# RB_Audio.net
KiCad netlist of a schematic drawn in Altium Designer
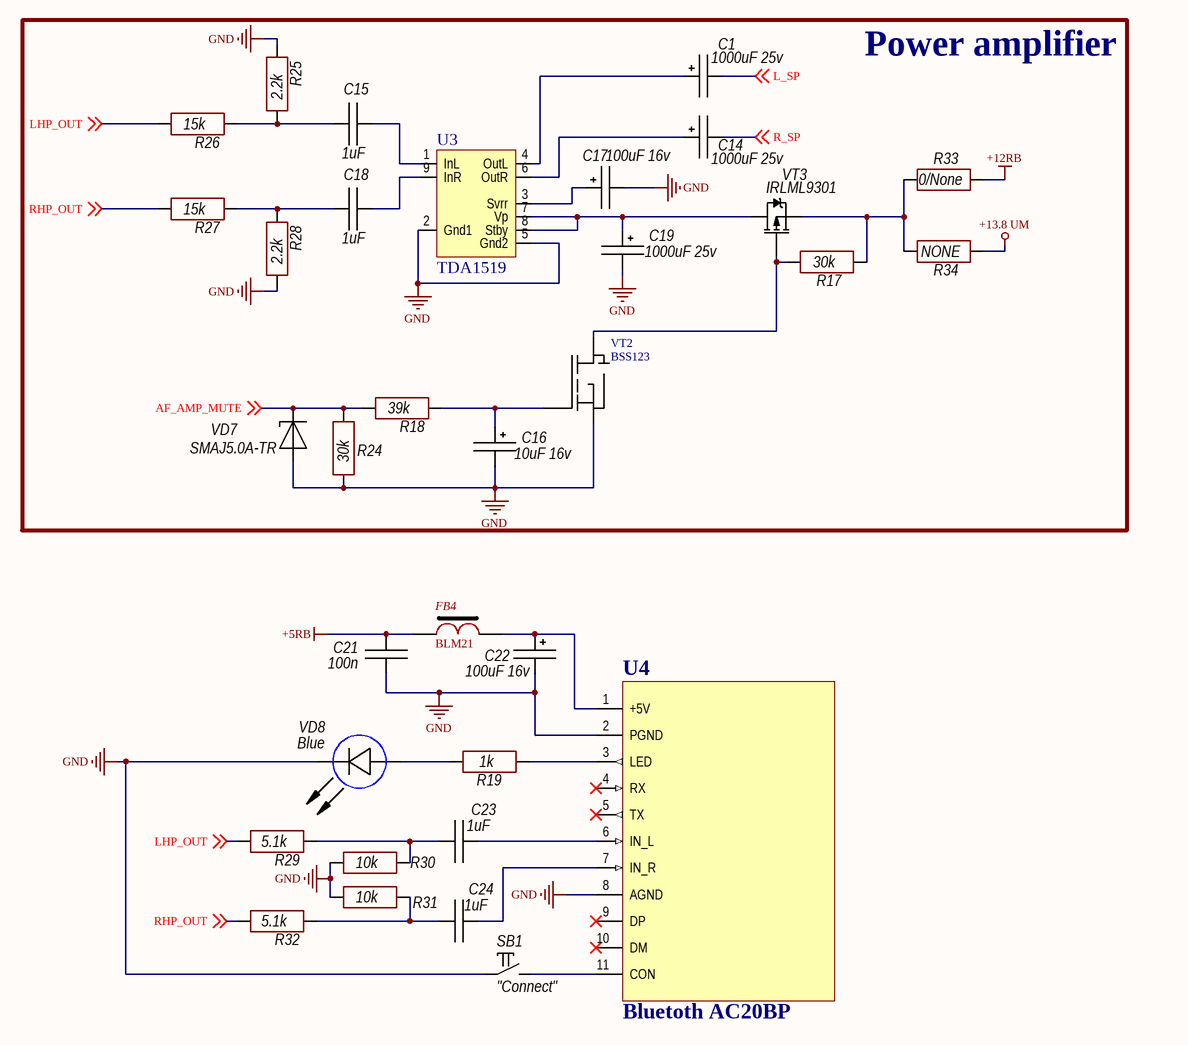
[diagram p0: RB_Audio.SchDoc]

(export (version "E")
  (design (tool "Eeschema 10.0.6"))
  (components
    (comp (ref "C1")
      (value "1000uF 25v")
      (footprint "standard:D10C5H12.5")
      (libsource (lib "Discrete") (part "AlumCap"))
    )
    (comp (ref "C14")
      (value "1000uF 25v")
      (footprint "standard:D10C5H12.5")
      (libsource (lib "") (part "AlumCap_1"))
    )
    (comp (ref "C15")
      (value "1uF")
      (footprint "standard:CH0805C")
      (libsource (lib "Discrete") (part "Capacitor"))
    )
    (comp (ref "C16")
      (value "10uF 16v")
      (footprint "standard:TANTAL_B")
      (libsource (lib "Discrete") (part "TantalCap"))
    )
    (comp (ref "C17")
      (value "100uF 16v")
      (footprint "standard:TANTAL_D")
      (libsource (lib "Discrete") (part "TantalCap"))
    )
    (comp (ref "C18")
      (value "1uF")
      (footprint "standard:CH0805C")
      (libsource (lib "Discrete") (part "Capacitor"))
    )
    (comp (ref "C19")
      (value "1000uF 25v")
      (footprint "standard:D10C5H12.5")
      (libsource (lib "Discrete") (part "AlumCap"))
    )
    (comp (ref "C21")
      (value "100n")
      (footprint "standard:CH0805C")
      (libsource (lib "Discrete") (part "Capacitor"))
    )
    (comp (ref "C22")
      (value "100uF 16v")
      (footprint "standard:D6.3C2.5H11")
      (libsource (lib "Discrete") (part "AlumCap"))
    )
    (comp (ref "C23")
      (value "1uF")
      (footprint "standard:CH0805C")
      (libsource (lib "Discrete") (part "Capacitor"))
    )
    (comp (ref "C24")
      (value "1uF")
      (footprint "standard:CH0805C")
      (libsource (lib "Discrete") (part "Capacitor"))
    )
    (comp (ref "FB4") (value "BLM21") (footprint "CH0805L") (libsource (lib "Discrete") (part "FB-1")))
    (comp (ref "R17") (value "30k") (footprint "standard:CH0805R") (libsource (lib "") (part "Resistor_1")))
    (comp (ref "R18") (value "39k") (footprint "standard:CH0805R") (libsource (lib "") (part "Resistor_1")))
    (comp (ref "R19") (value "1k") (footprint "standard:CH0805R") (libsource (lib "") (part "Resistor_1")))
    (comp (ref "R24")
      (value "30k")
      (footprint "standard:CH0805R")
      (libsource (lib "Discrete") (part "Resistor"))
    )
    (comp (ref "R25")
      (value "2.2k")
      (footprint "standard:CH0805R")
      (libsource (lib "Discrete") (part "Resistor"))
    )
    (comp (ref "R26") (value "15k") (footprint "standard:CH0805R") (libsource (lib "") (part "Resistor_1")))
    (comp (ref "R27") (value "15k") (footprint "standard:CH0805R") (libsource (lib "") (part "Resistor_1")))
    (comp (ref "R28") (value "2.2k") (footprint "standard:CH0805R") (libsource (lib "") (part "Resistor_2")))
    (comp (ref "R29") (value "5.1k") (footprint "standard:CH0805R") (libsource (lib "") (part "Resistor_1")))
    (comp (ref "R30") (value "10k") (footprint "standard:CH0805R") (libsource (lib "") (part "Resistor_1")))
    (comp (ref "R31") (value "10k") (footprint "standard:CH0805R") (libsource (lib "") (part "Resistor_1")))
    (comp (ref "R32") (value "5.1k") (footprint "standard:CH0805R") (libsource (lib "") (part "Resistor_1")))
    (comp (ref "R33")
      (value "0/None")
      (footprint "standard:CH1206R")
      (libsource (lib "") (part "Resistor_1"))
    )
    (comp (ref "R34") (value "NONE") (footprint "standard:CH1206R") (libsource (lib "") (part "Resistor_1")))
    (comp (ref "SB1")
      (value "\"Connect\"")
      (footprint "custom:BUT: 6x6 mm (R)")
      (description "6x6 mm")
      (libsource (lib "Connectors") (part "Tactile switches"))
    )
    (comp (ref "U3") (value "TDA1519") (footprint "SOT110B") (libsource (lib "Discrete") (part "TDA1519")))
    (comp (ref "U4")
      (value "Bluetoth AC20BP")
      (footprint "Bluetooth 11PIN")
      (libsource (lib "Module") (part "Bluetoth AC20BP Module"))
    )
    (comp (ref "VD7")
      (value "SMAJ5.0A-TR")
      (footprint "standard:SMA")
      (libsource (lib "Diods") (part "Diod Zener"))
    )
    (comp (ref "VD8")
      (value "Blue")
      (footprint "standard:CH0805LB")
      (libsource (lib "Discrete") (part "LED"))
    )
    (comp (ref "VT2") (value "BSS123") (footprint "SOT23_132") (libsource (lib "Transistor") (part "BSS123")))
    (comp (ref "VT3")
      (value "IRLML9301")
      (footprint "standard:SOT23_132")
      (description "Mosfet")
      (libsource (lib "Transistor") (part "IRLML9301"))
    )
  )
  (nets
    (net (code "1") (name "+5RB") (class "Default")
      (node (ref "C21") (pin "2") (pinfunction "2_2") (pintype "power_in"))
      (node (ref "FB4") (pin "2") (pinfunction "2_2") (pintype "passive"))
    )
    (net (code "2") (name "+12RB") (class "Default")
      (node (ref "R33") (pin "2") (pinfunction "2_2") (pintype "passive"))
    )
    (net (code "3") (name "+13.8 UM") (class "Default")
      (node (ref "R34") (pin "2") (pinfunction "2_2") (pintype "passive"))
    )
    (net (code "4") (name "AF_AMP_MUTE") (class "Default")
      (node (ref "R18") (pin "1") (pinfunction "1_1") (pintype "passive"))
      (node (ref "R24") (pin "2") (pinfunction "2_2") (pintype "passive"))
      (node (ref "VD7") (pin "2") (pinfunction "C_2") (pintype "passive"))
    )
    (net (code "5") (name "GND") (class "Default")
      (node (ref "C16") (pin "2") (pinfunction "2_2") (pintype "power_in"))
      (node (ref "C17") (pin "2") (pinfunction "2_2") (pintype "power_in"))
      (node (ref "C19") (pin "2") (pinfunction "2_2") (pintype "power_in"))
      (node (ref "C21") (pin "1") (pinfunction "1_1") (pintype "power_in"))
      (node (ref "C22") (pin "2") (pinfunction "2_2") (pintype "power_in"))
      (node (ref "R24") (pin "1") (pinfunction "1_1") (pintype "passive"))
      (node (ref "R25") (pin "2") (pinfunction "2_2") (pintype "passive"))
      (node (ref "R28") (pin "1") (pinfunction "1_1") (pintype "passive"))
      (node (ref "R30") (pin "1") (pinfunction "1_1") (pintype "passive"))
      (node (ref "R31") (pin "1") (pinfunction "1_1") (pintype "passive"))
      (node (ref "SB1") (pin "1") (pinfunction "1_1") (pintype "passive"))
      (node (ref "U3") (pin "2") (pinfunction "Gnd1_2") (pintype "passive"))
      (node (ref "U3") (pin "5") (pinfunction "Gnd2_5") (pintype "passive"))
      (node (ref "U4") (pin "2") (pinfunction "PGND_2") (pintype "passive"))
      (node (ref "U4") (pin "8") (pinfunction "AGND_8") (pintype "passive"))
      (node (ref "VD7") (pin "1") (pinfunction "A_1") (pintype "passive"))
      (node (ref "VD8") (pin "2") (pinfunction "C_2") (pintype "passive"))
      (node (ref "VT2") (pin "2") (pinfunction "S_2") (pintype "passive"))
    )
    (net (code "6") (name "LHP_OUT") (class "Default")
      (node (ref "R26") (pin "1") (pinfunction "1_1") (pintype "passive"))
      (node (ref "R29") (pin "1") (pinfunction "1_1") (pintype "passive"))
    )
    (net (code "7") (name "L_SP") (class "Default")
      (node (ref "C1") (pin "2") (pinfunction "2_2") (pintype "power_in"))
    )
    (net (code "8") (name "Net-(C15-Pad1)") (class "Default")
      (node (ref "C15") (pin "1") (pinfunction "1_1") (pintype "power_in"))
      (node (ref "R25") (pin "1") (pinfunction "1_1") (pintype "passive"))
      (node (ref "R26") (pin "2") (pinfunction "2_2") (pintype "passive"))
    )
    (net (code "9") (name "Net-(C18-Pad1)") (class "Default")
      (node (ref "C18") (pin "1") (pinfunction "1_1") (pintype "power_in"))
      (node (ref "R27") (pin "2") (pinfunction "2_2") (pintype "passive"))
      (node (ref "R28") (pin "2") (pinfunction "2_2") (pintype "passive"))
    )
    (net (code "10") (name "Net-(C23-Pad1)") (class "Default")
      (node (ref "C23") (pin "1") (pinfunction "1_1") (pintype "power_in"))
      (node (ref "R29") (pin "2") (pinfunction "2_2") (pintype "passive"))
      (node (ref "R30") (pin "2") (pinfunction "2_2") (pintype "passive"))
    )
    (net (code "11") (name "Net-(C24-Pad1)") (class "Default")
      (node (ref "C24") (pin "1") (pinfunction "1_1") (pintype "power_in"))
      (node (ref "R31") (pin "2") (pinfunction "2_2") (pintype "passive"))
      (node (ref "R32") (pin "2") (pinfunction "2_2") (pintype "passive"))
    )
    (net (code "12") (name "Net-(U3-InL)") (class "Default")
      (node (ref "C15") (pin "2") (pinfunction "2_2") (pintype "power_in"))
      (node (ref "U3") (pin "1") (pinfunction "InL_1") (pintype "passive"))
    )
    (net (code "13") (name "Net-(U3-InR)") (class "Default")
      (node (ref "C18") (pin "2") (pinfunction "2_2") (pintype "power_in"))
      (node (ref "U3") (pin "9") (pinfunction "InR_9") (pintype "passive"))
    )
    (net (code "14") (name "Net-(U3-OutL)") (class "Default")
      (node (ref "C1") (pin "1") (pinfunction "1_1") (pintype "power_in"))
      (node (ref "U3") (pin "4") (pinfunction "OutL_4") (pintype "passive"))
    )
    (net (code "15") (name "Net-(U3-OutR)") (class "Default")
      (node (ref "C14") (pin "1") (pinfunction "1_1") (pintype "power_in"))
      (node (ref "U3") (pin "6") (pinfunction "OutR_6") (pintype "passive"))
    )
    (net (code "16") (name "Net-(U3-Stby)") (class "Default")
      (node (ref "C19") (pin "1") (pinfunction "1_1") (pintype "power_in"))
      (node (ref "U3") (pin "7") (pinfunction "Vp_7") (pintype "passive"))
      (node (ref "U3") (pin "8") (pinfunction "Stby_8") (pintype "passive"))
      (node (ref "VT3") (pin "3") (pinfunction "D_3") (pintype "passive"))
    )
    (net (code "17") (name "Net-(U3-Svrr)") (class "Default")
      (node (ref "C17") (pin "1") (pinfunction "1_1") (pintype "power_in"))
      (node (ref "U3") (pin "3") (pinfunction "Svrr_3") (pintype "passive"))
    )
    (net (code "18") (name "Net-(U4-+5V)") (class "Default")
      (node (ref "C22") (pin "1") (pinfunction "1_1") (pintype "power_in"))
      (node (ref "FB4") (pin "1") (pinfunction "1_1") (pintype "passive"))
      (node (ref "U4") (pin "1") (pinfunction "+5V_1") (pintype "power_in"))
    )
    (net (code "19") (name "Net-(U4-CON)") (class "Default")
      (node (ref "SB1") (pin "2") (pinfunction "2_2") (pintype "passive"))
      (node (ref "U4") (pin "11") (pinfunction "CON_11") (pintype "passive"))
    )
    (net (code "20") (name "Net-(U4-IN_L)") (class "Default")
      (node (ref "C23") (pin "2") (pinfunction "2_2") (pintype "power_in"))
      (node (ref "U4") (pin "6") (pinfunction "IN_L_6") (pintype "input"))
    )
    (net (code "21") (name "Net-(U4-IN_R)") (class "Default")
      (node (ref "C24") (pin "2") (pinfunction "2_2") (pintype "power_in"))
      (node (ref "U4") (pin "7") (pinfunction "IN_R_7") (pintype "input"))
    )
    (net (code "22") (name "Net-(U4-LED)") (class "Default")
      (node (ref "R19") (pin "2") (pinfunction "2_2") (pintype "passive"))
      (node (ref "U4") (pin "3") (pinfunction "LED_3") (pintype "output"))
    )
    (net (code "23") (name "Net-(VD8-A)") (class "Default")
      (node (ref "R19") (pin "1") (pinfunction "1_1") (pintype "passive"))
      (node (ref "VD8") (pin "1") (pinfunction "A_1") (pintype "passive"))
    )
    (net (code "24") (name "Net-(VT2-D)") (class "Default")
      (node (ref "R17") (pin "1") (pinfunction "1_1") (pintype "passive"))
      (node (ref "VT2") (pin "3") (pinfunction "D_3") (pintype "passive"))
      (node (ref "VT3") (pin "1") (pinfunction "G_1") (pintype "passive"))
    )
    (net (code "25") (name "Net-(VT2-G)") (class "Default")
      (node (ref "C16") (pin "1") (pinfunction "1_1") (pintype "power_in"))
      (node (ref "R18") (pin "2") (pinfunction "2_2") (pintype "passive"))
      (node (ref "VT2") (pin "1") (pinfunction "G_1") (pintype "passive"))
    )
    (net (code "26") (name "Net-(VT3-S)") (class "Default")
      (node (ref "R17") (pin "2") (pinfunction "2_2") (pintype "passive"))
      (node (ref "R33") (pin "1") (pinfunction "1_1") (pintype "passive"))
      (node (ref "R34") (pin "1") (pinfunction "1_1") (pintype "passive"))
      (node (ref "VT3") (pin "2") (pinfunction "S_2") (pintype "passive"))
    )
    (net (code "27") (name "RHP_OUT") (class "Default")
      (node (ref "R27") (pin "1") (pinfunction "1_1") (pintype "passive"))
      (node (ref "R32") (pin "1") (pinfunction "1_1") (pintype "passive"))
    )
    (net (code "28") (name "R_SP") (class "Default")
      (node (ref "C14") (pin "2") (pinfunction "2_2") (pintype "power_in"))
    )
    (net (code "29") (name "unconnected-(U4-DM-Pad10)") (class "Default")
      (node (ref "U4") (pin "10") (pinfunction "DM_10") (pintype "passive+no_connect"))
    )
    (net (code "30") (name "unconnected-(U4-DP-Pad9)") (class "Default")
      (node (ref "U4") (pin "9") (pinfunction "DP_9") (pintype "passive+no_connect"))
    )
    (net (code "31") (name "unconnected-(U4-RX-Pad4)") (class "Default")
      (node (ref "U4") (pin "4") (pinfunction "RX_4") (pintype "input+no_connect"))
    )
    (net (code "32") (name "unconnected-(U4-TX-Pad5)") (class "Default")
      (node (ref "U4") (pin "5") (pinfunction "TX_5") (pintype "output+no_connect"))
    )
  )
)
